# VoedingBat20V.net
KiCad netlist of a schematic drawn in Altium Designer
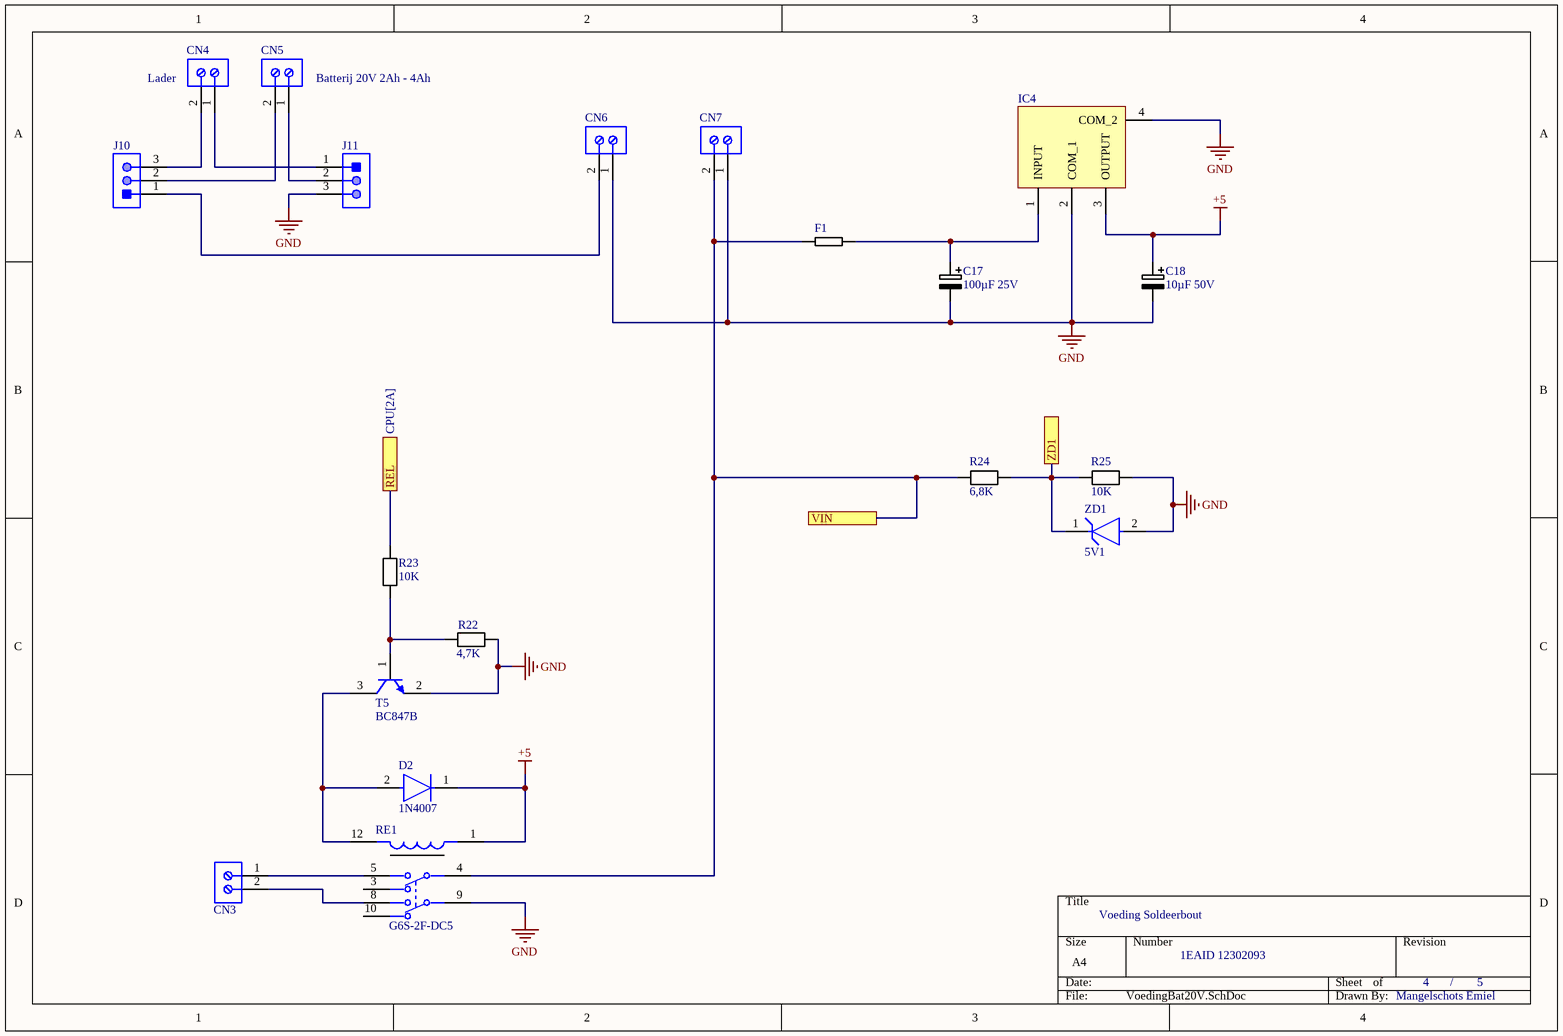
[diagram p0: VoedingBat20V.SchDoc]

(export (version "E")
  (design (tool "Eeschema 10.0.6"))
  (components
    (comp (ref "C17")
      (value "100µF 25V")
      (footprint "CAPA1")
      (fields (field (name "PART NUMBER") "GRM1885C1H100JA01D") (field (name "MANUFACTURER") "Murata"))
      (libsource (lib "Schlib1") (part "Capasitor_1"))
    )
    (comp (ref "C18")
      (value "10µF 50V")
      (footprint "CAPA1")
      (fields (field (name "PART NUMBER") "GRM1885C1H100JA01D") (field (name "MANUFACTURER") "Murata"))
      (libsource (lib "Schlib1") (part "Capasitor_1"))
    )
    (comp (ref "CN3")
      (value "1725656")
      (footprint "2 pinHeader")
      (fields (field (name "MANUFACTURER") "Phoenix Contact"))
      (libsource (lib "Schlib1") (part "2Pin-Header"))
    )
    (comp (ref "CN4")
      (value "Lader")
      (footprint "2 pinHeader")
      (fields
        (field (name "MANUFACTURER PART NO.") "1725656")
        (field (name "MANUFACTURER") "Phoenix Contact")
      )
      (libsource (lib "Schlib1") (part "2Pin-Header"))
    )
    (comp (ref "CN5")
      (value "Batterij 20V 2Ah - 4Ah")
      (footprint "2 pinHeader")
      (fields
        (field (name "MANUFACTURER PART NO.") "1725656")
        (field (name "MANUFACTURER") "Phoenix Contact")
      )
      (libsource (lib "Schlib1") (part "2Pin-Header"))
    )
    (comp (ref "CN6")
      (value "1725656")
      (footprint "2 pinHeader")
      (fields (field (name "MANUFACTURER") "Phoenix Contact"))
      (libsource (lib "Schlib1") (part "2Pin-Header"))
    )
    (comp (ref "CN7")
      (value "1725656")
      (footprint "2 pinHeader")
      (fields (field (name "MANUFACTURER") "Phoenix Contact"))
      (libsource (lib "Schlib1") (part "2Pin-Header"))
    )
    (comp (ref "D2")
      (value "1N4007")
      (footprint "DIOD")
      (description "1N4001-E3/54")
      (fields (field (name "VOLTAGE") "50V"))
      (libsource (lib "Schlib1") (part "Diode"))
    )
    (comp (ref "F1") (value "F1") (footprint "F1") (libsource (lib "Schlib1") (part "F1")))
    (comp (ref "IC4")
      (value "OKI-78SR-5/1.5-W36-C")
      (footprint "SIP625W50P254L1173H771Q4")
      (fields (field (name "MANUFACTURER") "Murata"))
      (libsource (lib "Schlib1") (part "IC"))
    )
    (comp (ref "J10")
      (value "B3B-PH-K-S(LF)(SN)")
      (footprint "3PinH")
      (fields (field (name "MANUFACTURER") "JST"))
      (libsource (lib "Schlib1") (part "3Pin-Header"))
    )
    (comp (ref "J11")
      (value "B3B-PH-K-S(LF)(SN)")
      (footprint "3PinH")
      (fields (field (name "MANUFACTURER") "JST"))
      (libsource (lib "") (part "3Pin-Header_1"))
    )
    (comp (ref "K1")
      (value "G6S-2F-DC5")
      (footprint "VermogenRelais")
      (fields
        (field (name "MANUFACTURER PART NUMBER") "RT424005")
        (field (name "OCTOPART") "https://octopart.com/5-1393243-9-te+connectivity-41835766")
        (field (name "MANUFACTURER") "TE Connectivity")
      )
      (libsource (lib "Schlib1") (part "VermogenRelais"))
    )
    (comp (ref "R22")
      (value "4,7K")
      (footprint "REST")
      (fields (field (name "MANUFACTURER") "Vishay Dale") (field (name "PART NUMBER") "CRCW08050000Z0EA"))
      (libsource (lib "Schlib1") (part "resistor"))
    )
    (comp (ref "R23")
      (value "10K")
      (footprint "REST")
      (fields (field (name "MANUFACTURER") "Vishay Dale") (field (name "PART NUMBER") "CRCW08050000Z0EA"))
      (libsource (lib "Schlib1") (part "resistor"))
    )
    (comp (ref "R24")
      (value "6,8K")
      (footprint "REST")
      (fields (field (name "MANUFACTURER") "Vishay Dale") (field (name "PART NUMBER") "CRCW08050000Z0EA"))
      (libsource (lib "Schlib1") (part "resistor"))
    )
    (comp (ref "R25")
      (value "10K")
      (footprint "REST")
      (fields (field (name "MANUFACTURER") "Vishay Dale") (field (name "PART NUMBER") "CRCW08050000Z0EA"))
      (libsource (lib "Schlib1") (part "resistor"))
    )
    (comp (ref "RE1")
      (value "SmoorSpoel")
      (footprint "Smoorspoel")
      (fields (field (name "MP") "NLV25T-100J-EF") (field (name "MF") "TDK"))
      (libsource (lib "Schlib1") (part "SmoorSpoel"))
    )
    (comp (ref "T5")
      (value "BC847B")
      (footprint "TRANS")
      (fields (field (name "MANUFACTURER") "On Semiconductor") (field (name "PARTNUMBER") "BC547C"))
      (libsource (lib "Schlib1") (part "Transistor"))
    )
    (comp (ref "ZD1") (value "5V1") (footprint "ZEN") (libsource (lib "Schlib1") (part "Zenerdiode")))
  )
  (nets
    (net (code "1") (name "+5") (class "Default")
      (node (ref "C18") (pin "1") (pinfunction "1_1") (pintype "passive"))
      (node (ref "D2") (pin "1") (pinfunction "C_1") (pintype "passive"))
      (node (ref "IC4") (pin "3") (pinfunction "OUTPUT_3") (pintype "power_in"))
      (node (ref "RE1") (pin "1") (pintype "passive"))
    )
    (net (code "2") (name "/REL") (class "Default")
      (node (ref "R23") (pin "2") (pinfunction "2_2") (pintype "passive"))
    )
    (net (code "3") (name "/VIN") (class "Default")
      (node (ref "CN7") (pin "2") (pinfunction "2_2") (pintype "passive"))
      (node (ref "F1") (pin "1") (pinfunction "1_1") (pintype "passive"))
      (node (ref "K1") (pin "4") (pinfunction "4_4") (pintype "passive"))
      (node (ref "R24") (pin "1") (pinfunction "1_1") (pintype "passive"))
    )
    (net (code "4") (name "/ZD1") (class "Default")
      (node (ref "R24") (pin "2") (pinfunction "2_2") (pintype "passive"))
      (node (ref "R25") (pin "1") (pinfunction "1_1") (pintype "passive"))
      (node (ref "ZD1") (pin "1") (pinfunction "C_1") (pintype "passive"))
    )
    (net (code "5") (name "GND") (class "Default")
      (node (ref "C17") (pin "2") (pinfunction "2_2") (pintype "passive"))
      (node (ref "C18") (pin "2") (pinfunction "2_2") (pintype "passive"))
      (node (ref "CN6") (pin "1") (pinfunction "1_1") (pintype "passive"))
      (node (ref "CN7") (pin "1") (pinfunction "1_1") (pintype "passive"))
      (node (ref "IC4") (pin "2") (pinfunction "COM_1_2") (pintype "power_in"))
      (node (ref "IC4") (pin "4") (pinfunction "COM_2_4") (pintype "power_in"))
      (node (ref "J11") (pin "3") (pinfunction "3_3") (pintype "passive"))
      (node (ref "K1") (pin "9") (pinfunction "9_9") (pintype "passive"))
      (node (ref "R22") (pin "2") (pinfunction "2_2") (pintype "passive"))
      (node (ref "R25") (pin "2") (pinfunction "2_2") (pintype "passive"))
      (node (ref "T5") (pin "2") (pinfunction "E_2") (pintype "passive"))
      (node (ref "ZD1") (pin "2") (pinfunction "A_2") (pintype "passive"))
    )
    (net (code "6") (name "Net-(CN3-Pad1)") (class "Default")
      (node (ref "CN3") (pin "1") (pinfunction "1_1") (pintype "passive"))
      (node (ref "K1") (pin "5") (pinfunction "5_5") (pintype "passive"))
    )
    (net (code "7") (name "Net-(CN3-Pad2)") (class "Default")
      (node (ref "CN3") (pin "2") (pinfunction "2_2") (pintype "passive"))
      (node (ref "K1") (pin "8") (pinfunction "8_8") (pintype "passive"))
    )
    (net (code "8") (name "Net-(CN4-Pad1)") (class "Default")
      (node (ref "CN4") (pin "1") (pinfunction "1_1") (pintype "passive"))
      (node (ref "J11") (pin "1") (pinfunction "1_1") (pintype "passive"))
    )
    (net (code "9") (name "Net-(CN4-Pad2)") (class "Default")
      (node (ref "CN4") (pin "2") (pinfunction "2_2") (pintype "passive"))
      (node (ref "J10") (pin "3") (pinfunction "3_3") (pintype "passive"))
    )
    (net (code "10") (name "Net-(CN5-Pad1)") (class "Default")
      (node (ref "CN5") (pin "1") (pinfunction "1_1") (pintype "passive"))
      (node (ref "J11") (pin "2") (pinfunction "2_2") (pintype "passive"))
    )
    (net (code "11") (name "Net-(CN5-Pad2)") (class "Default")
      (node (ref "CN5") (pin "2") (pinfunction "2_2") (pintype "passive"))
      (node (ref "J10") (pin "2") (pinfunction "2_2") (pintype "passive"))
    )
    (net (code "12") (name "Net-(CN6-Pad2)") (class "Default")
      (node (ref "CN6") (pin "2") (pinfunction "2_2") (pintype "passive"))
      (node (ref "J10") (pin "1") (pinfunction "1_1") (pintype "passive"))
    )
    (net (code "13") (name "Net-(D2-A)") (class "Default")
      (node (ref "D2") (pin "2") (pinfunction "A_2") (pintype "passive"))
      (node (ref "RE1") (pin "12") (pinfunction "12_12") (pintype "passive"))
      (node (ref "T5") (pin "3") (pinfunction "C_3") (pintype "passive"))
    )
    (net (code "14") (name "Net-(IC4-INPUT)") (class "Default")
      (node (ref "C17") (pin "1") (pinfunction "1_1") (pintype "passive"))
      (node (ref "F1") (pin "2") (pinfunction "1_2") (pintype "passive"))
      (node (ref "IC4") (pin "1") (pinfunction "INPUT_1") (pintype "power_in"))
    )
    (net (code "15") (name "Net-(T5-B)") (class "Default")
      (node (ref "R22") (pin "1") (pinfunction "1_1") (pintype "passive"))
      (node (ref "R23") (pin "1") (pinfunction "1_1") (pintype "passive"))
      (node (ref "T5") (pin "1") (pinfunction "B_1") (pintype "passive"))
    )
    (net (code "16") (name "unconnected-(K1-Pad3)") (class "Default")
      (node (ref "K1") (pin "3") (pinfunction "3_3") (pintype "passive"))
    )
    (net (code "17") (name "unconnected-(K1-Pad10)") (class "Default")
      (node (ref "K1") (pin "10") (pinfunction "10_10") (pintype "passive"))
    )
  )
)
